# 51PCB_Project.net
KiCad netlist of a schematic drawn in EasyEDA Pro
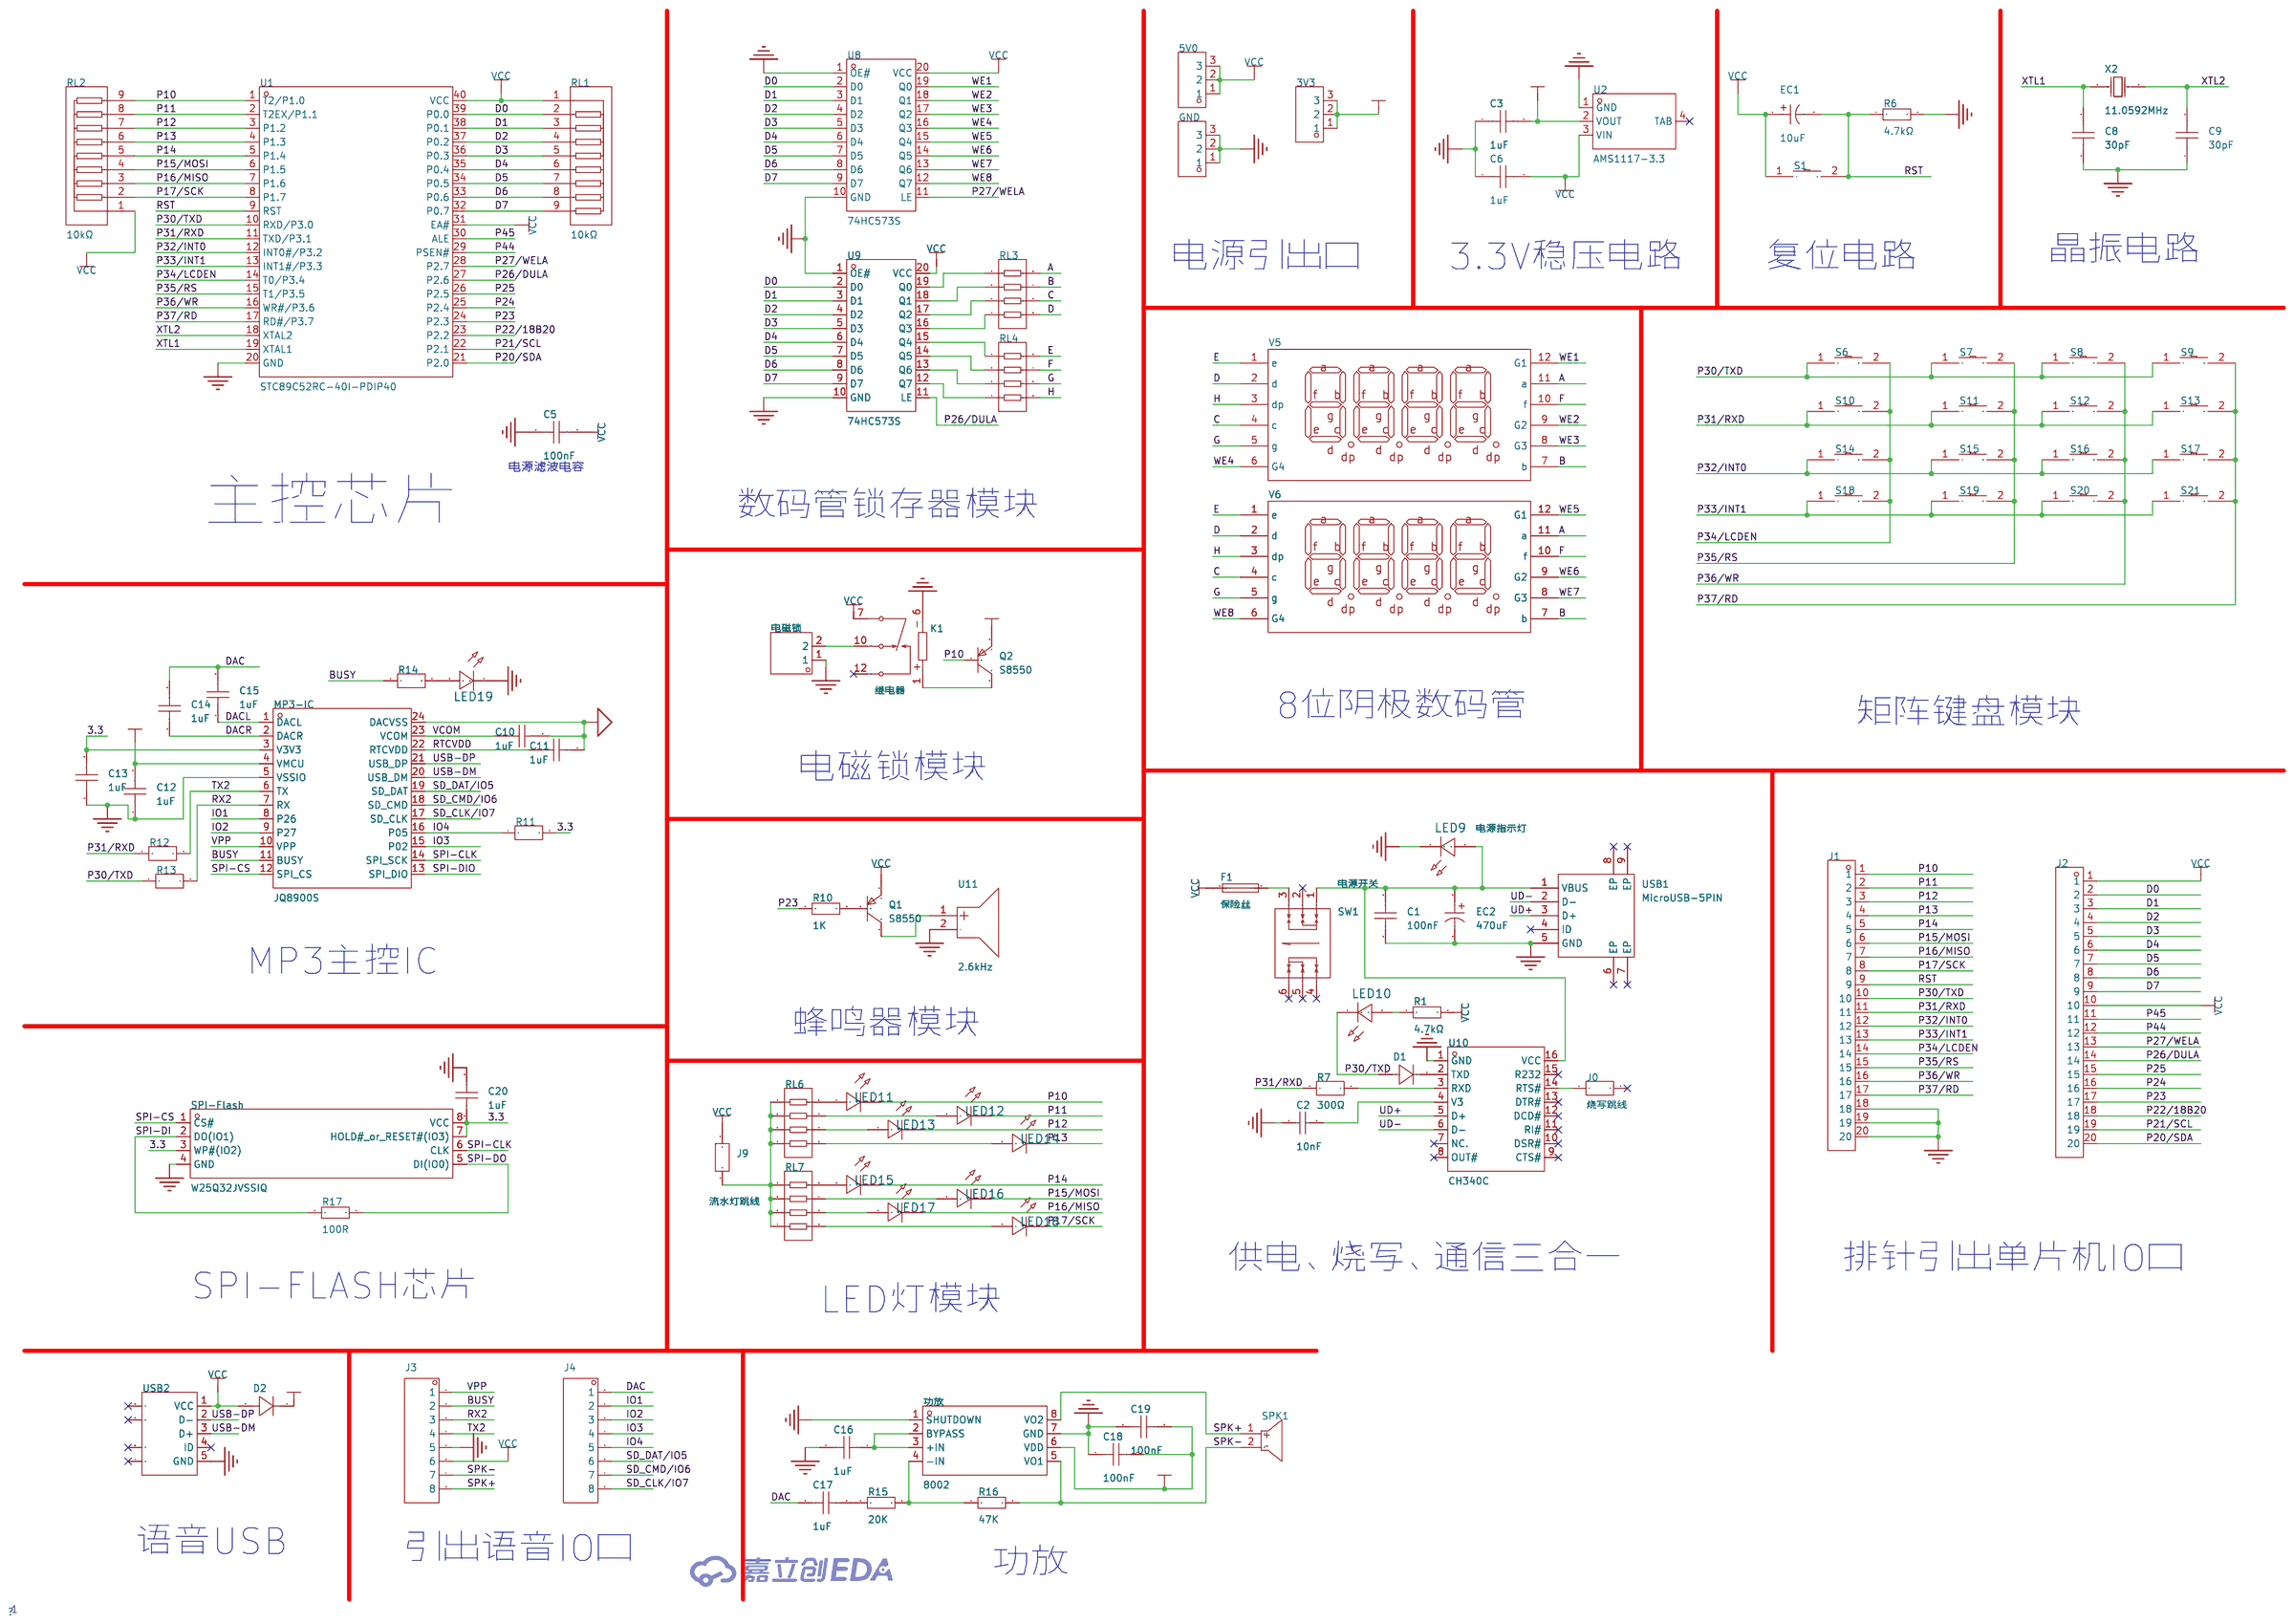
[diagram p0: schematic sheet]

(export (version "E")
  (design (tool "Eeschema 10.0.6"))
  (components
    (comp (ref "3V3")
      (value "~")
      (footprint "easyedapro:HDR-TH_3P-P2.54-V-M")
      (libsource (lib "easyedapro") (part "PZ254V-11-03P_C2937625"))
    )
    (comp (ref "5V0")
      (value "~")
      (footprint "easyedapro:HDR-TH_3P-P2.54-V-M")
      (libsource (lib "easyedapro") (part "PZ254V-11-03P_C2937625"))
    )
    (comp (ref "C1")
      (value "100nF")
      (footprint "easyedapro:CAP-TH_L6.5-W3.5-P2.50-D0.6-S2.90")
      (description "容值:100nF;精度:-20%~+80%;额定电压:50V;温度系数:Y5V;")
      (fields
        (field (name "Manufacturer Part") "CC1H104ZA1FD3F6C1100")
        (field (name "Manufacturer") "Dersonic(德尔创)")
      )
      (libsource (lib "easyedapro") (part "CC1H104ZA1FD3F6C1100"))
    )
    (comp (ref "C2")
      (value "10nF")
      (footprint "easyedapro:C1206")
      (description "容值:10nF;精度:±10%;额定电压:50V;材质(温度系数):X7R;")
      (fields (field (name "Manufacturer Part") "1206B103K500NT") (field (name "Manufacturer") "FH(风华)"))
      (libsource (lib "easyedapro") (part "1206B103K500NT"))
    )
    (comp (ref "C3")
      (value "1uF")
      (footprint "easyedapro:CAP-TH_L5.5-W3.5-P5.00-D1.2")
      (description "容值:1uF;精度:±10%;额定电压:50V;温度系数:X7R;")
      (fields (field (name "Manufacturer Part") "FK26X7R1H105KRE06") (field (name "Manufacturer") "TDK"))
      (libsource (lib "easyedapro") (part "FK26X7R1H105KRE06"))
    )
    (comp (ref "C5")
      (value "100nF")
      (footprint "easyedapro:CAP-TH_L5.0-W2.5-P5.00-D1.0")
      (description "容值:100nF;精度:±20%;额定电压:50V;温度系数:Y5V;")
      (fields
        (field (name "Manufacturer Part") "CC1H104MC1FD3F6C10MF")
        (field (name "Manufacturer") "Dersonic(德尔创)")
      )
      (libsource (lib "easyedapro") (part "CC1H104MC1FD3F6C10MF"))
    )
    (comp (ref "C6")
      (value "1uF")
      (footprint "easyedapro:CAP-TH_L5.5-W3.5-P5.00-D1.2")
      (description "容值:1uF;精度:±10%;额定电压:50V;温度系数:X7R;")
      (fields (field (name "Manufacturer Part") "FK26X7R1H105KRE06") (field (name "Manufacturer") "TDK"))
      (libsource (lib "easyedapro") (part "FK26X7R1H105KRE06"))
    )
    (comp (ref "C8")
      (value "30pF")
      (footprint "easyedapro:CAP-TH_L5.0-W3.0-P5.00-D1.0")
      (description "容值:30pF;精度:±5%;额定电压:50V;温度系数:-;")
      (fields
        (field (name "Manufacturer Part") "DCC300J20COHF6FJ5A0")
        (field (name "Manufacturer") "SHM(南方宏明)")
      )
      (libsource (lib "easyedapro") (part "DCC300J20COHF6FJ5A0"))
    )
    (comp (ref "C9")
      (value "30pF")
      (footprint "easyedapro:CAP-TH_L5.0-W3.0-P5.00-D1.0")
      (description "容值:30pF;精度:±5%;额定电压:50V;温度系数:-;")
      (fields
        (field (name "Manufacturer Part") "DCC300J20COHF6FJ5A0")
        (field (name "Manufacturer") "SHM(南方宏明)")
      )
      (libsource (lib "easyedapro") (part "DCC300J20COHF6FJ5A0"))
    )
    (comp (ref "C10")
      (value "1uF")
      (footprint "easyedapro:CAP-TH_L5.5-W3.5-P5.00-D1.2")
      (description "容值:1uF;精度:±10%;额定电压:50V;温度系数:X7R;")
      (fields (field (name "Manufacturer Part") "FK26X7R1H105KRE06") (field (name "Manufacturer") "TDK"))
      (libsource (lib "easyedapro") (part "FK26X7R1H105KRE06"))
    )
    (comp (ref "C11")
      (value "1uF")
      (footprint "easyedapro:CAP-TH_L5.5-W3.5-P5.00-D1.2")
      (description "容值:1uF;精度:±10%;额定电压:50V;温度系数:X7R;")
      (fields (field (name "Manufacturer Part") "FK26X7R1H105KRE06") (field (name "Manufacturer") "TDK"))
      (libsource (lib "easyedapro") (part "FK26X7R1H105KRE06"))
    )
    (comp (ref "C12")
      (value "1uF")
      (footprint "easyedapro:CAP-TH_L5.5-W3.5-P5.00-D1.2")
      (description "容值:1uF;精度:±10%;额定电压:50V;温度系数:X7R;")
      (fields (field (name "Manufacturer Part") "FK26X7R1H105KRE06") (field (name "Manufacturer") "TDK"))
      (libsource (lib "easyedapro") (part "FK26X7R1H105KRE06"))
    )
    (comp (ref "C13")
      (value "1uF")
      (footprint "easyedapro:CAP-TH_L5.5-W3.5-P5.00-D1.2")
      (description "容值:1uF;精度:±10%;额定电压:50V;温度系数:X7R;")
      (fields (field (name "Manufacturer Part") "FK26X7R1H105KRE06") (field (name "Manufacturer") "TDK"))
      (libsource (lib "easyedapro") (part "FK26X7R1H105KRE06"))
    )
    (comp (ref "C14")
      (value "1uF")
      (footprint "easyedapro:CAP-TH_L5.5-W3.5-P5.00-D1.2")
      (description "容值:1uF;精度:±10%;额定电压:50V;温度系数:X7R;")
      (fields (field (name "Manufacturer Part") "FK26X7R1H105KRE06") (field (name "Manufacturer") "TDK"))
      (libsource (lib "easyedapro") (part "FK26X7R1H105KRE06"))
    )
    (comp (ref "C15")
      (value "1uF")
      (footprint "easyedapro:CAP-TH_L5.5-W3.5-P5.00-D1.2")
      (description "容值:1uF;精度:±10%;额定电压:50V;温度系数:X7R;")
      (fields (field (name "Manufacturer Part") "FK26X7R1H105KRE06") (field (name "Manufacturer") "TDK"))
      (libsource (lib "easyedapro") (part "FK26X7R1H105KRE06"))
    )
    (comp (ref "C16")
      (value "1uF")
      (footprint "easyedapro:CAP-TH_L5.5-W3.5-P5.00-D1.2")
      (description "容值:1uF;精度:±10%;额定电压:50V;温度系数:X7R;")
      (fields (field (name "Manufacturer Part") "FK26X7R1H105KRE06") (field (name "Manufacturer") "TDK"))
      (libsource (lib "easyedapro") (part "FK26X7R1H105KRE06"))
    )
    (comp (ref "C17")
      (value "1uF")
      (footprint "easyedapro:CAP-TH_L5.5-W3.5-P5.00-D1.2")
      (description "容值:1uF;精度:±10%;额定电压:50V;温度系数:X7R;")
      (fields (field (name "Manufacturer Part") "FK26X7R1H105KRE06") (field (name "Manufacturer") "TDK"))
      (libsource (lib "easyedapro") (part "FK26X7R1H105KRE06"))
    )
    (comp (ref "C18")
      (value "100nF")
      (footprint "easyedapro:C0603")
      (libsource (lib "easyedapro") (part "CapAcitance"))
    )
    (comp (ref "C19")
      (value "100nF")
      (footprint "easyedapro:C0603")
      (libsource (lib "easyedapro") (part "CapAcitance"))
    )
    (comp (ref "C20")
      (value "1uF")
      (footprint "easyedapro:CAP-TH_L5.5-W3.5-P5.00-D1.2")
      (description "容值:1uF;精度:±10%;额定电压:50V;温度系数:X7R;")
      (fields (field (name "Manufacturer Part") "FK26X7R1H105KRE06") (field (name "Manufacturer") "TDK"))
      (libsource (lib "easyedapro") (part "FK26X7R1H105KRE06"))
    )
    (comp (ref "D1")
      (value "~")
      (footprint "easyedapro:DO_1N4007")
      (libsource (lib "easyedapro") (part "D_1N4007"))
    )
    (comp (ref "D2")
      (value "~")
      (footprint "easyedapro:DO_1N4007")
      (libsource (lib "easyedapro") (part "D_1N4007"))
    )
    (comp (ref "EC1")
      (value "10uF")
      (footprint "easyedapro:CAP-SMD_BD6.3-L6.6-W6.6-LS7.2-FD")
      (description "容值:10uF;精度:±20%;额定电压:50V;纹波电流:29mA@120Hz;")
      (fields
        (field (name "Manufacturer Part") "MVK50V10M6.3*5")
        (field (name "Manufacturer") "SAMYOUNG(韩国三莹)")
      )
      (libsource (lib "easyedapro") (part "MVK50V10UF06*05"))
    )
    (comp (ref "EC2")
      (value "470uF")
      (footprint "easyedapro:CAP-TH_BD16.0-P7.50-D1.2-FD")
      (description "容值:470uF;精度:±20%;额定电压:100V;纹波电流:2.4A@100kHz;等效串联电阻:33mΩ@100kHz;")
      (fields
        (field (name "Manufacturer Part") "NXH100VB470M16*31.5 LO")
        (field (name "Manufacturer") "SAMYOUNG(韩国三莹)")
      )
      (libsource (lib "easyedapro") (part "NXH100VB470M16*31.5 LO"))
    )
    (comp (ref "F1")
      (value "保险丝")
      (footprint "easyedapro:F1812")
      (description "最大电压:33V;最大电流:40A;保持电流:500mA;跳闸电流:1A;")
      (fields (field (name "Manufacturer") "BHFUSE(佰宏)"))
      (libsource (lib "easyedapro") (part "BSMD1812-050-33V"))
    )
    (comp (ref "GND")
      (value "~")
      (footprint "easyedapro:HDR-TH_3P-P2.54-V-M")
      (libsource (lib "easyedapro") (part "PZ254V-11-03P_C2937625"))
    )
    (comp (ref "J0")
      (value "烧写跳线")
      (footprint "easyedapro:CONN-TH_D3086XX")
      (fields (field (name "Manufacturer Part") "D3086-97") (field (name "Manufacturer") "Harwin"))
      (libsource (lib "easyedapro") (part "D3086-97"))
    )
    (comp (ref "J1")
      (value "~")
      (footprint "easyedapro:HDR-TH_20P-P2.54-V-M-1")
      (libsource (lib "easyedapro") (part "HDR_2.54-1x20P"))
    )
    (comp (ref "J2")
      (value "~")
      (footprint "easyedapro:HDR-TH_20P-P2.54-V-M-1")
      (libsource (lib "easyedapro") (part "HDR_2.54-1x20P"))
    )
    (comp (ref "J3")
      (value "~")
      (footprint "easyedapro:HDR-TH_8P-P2.54-V-M")
      (libsource (lib "easyedapro") (part "Header-Male-2.54_1x8"))
    )
    (comp (ref "J4")
      (value "~")
      (footprint "easyedapro:HDR-TH_8P-P2.54-V-M")
      (libsource (lib "easyedapro") (part "Header-Male-2.54_1x8"))
    )
    (comp (ref "J9")
      (value "流水灯跳线")
      (footprint "easyedapro:CONN-TH_D3086XX")
      (fields (field (name "Manufacturer") "Harwin"))
      (libsource (lib "easyedapro") (part "D3086-97"))
    )
    (comp (ref "K1")
      (value "继电器")
      (footprint "easyedapro:RELAY-TH_DS1E-S-DC24V")
      (description "线圈电压:12V;触点形式:一组转换:1C(单刀双掷-转换);触点容量(电阻负载):-;最大切换电压:250V@AC；220V@DC;最大切换电流:2A;")
      (fields (field (name "Manufacturer") "PANASONIC(松下)"))
      (libsource (lib "easyedapro") (part "DS1E-M-DC12V"))
    )
    (comp (ref "LED9")
      (value "电源指示灯")
      (footprint "easyedapro:LED_0805")
      (libsource (lib "easyedapro") (part "LED_R"))
    )
    (comp (ref "LED10")
      (value "~")
      (footprint "easyedapro:LED_0805")
      (libsource (lib "easyedapro") (part "LED_R"))
    )
    (comp (ref "LED11")
      (value "~")
      (footprint "easyedapro:LED_0805")
      (libsource (lib "easyedapro") (part "LED_R"))
    )
    (comp (ref "LED12")
      (value "~")
      (footprint "easyedapro:LED_0805")
      (libsource (lib "easyedapro") (part "LED_R"))
    )
    (comp (ref "LED13")
      (value "~")
      (footprint "easyedapro:LED_0805")
      (libsource (lib "easyedapro") (part "LED_R"))
    )
    (comp (ref "LED14")
      (value "~")
      (footprint "easyedapro:LED_0805")
      (libsource (lib "easyedapro") (part "LED_R"))
    )
    (comp (ref "LED15")
      (value "~")
      (footprint "easyedapro:LED_0805")
      (libsource (lib "easyedapro") (part "LED_R"))
    )
    (comp (ref "LED16")
      (value "~")
      (footprint "easyedapro:LED_0805")
      (libsource (lib "easyedapro") (part "LED_R"))
    )
    (comp (ref "LED17")
      (value "~")
      (footprint "easyedapro:LED_0805")
      (libsource (lib "easyedapro") (part "LED_R"))
    )
    (comp (ref "LED18")
      (value "~")
      (footprint "easyedapro:LED_0805")
      (libsource (lib "easyedapro") (part "LED_R"))
    )
    (comp (ref "LED19")
      (value "~")
      (footprint "easyedapro:LED_0805")
      (libsource (lib "easyedapro") (part "LED_R"))
    )
    (comp (ref "MP3-IC")
      (value "JQ8900S")
      (footprint "easyedapro:TSSOP-24_L7.8-W4.4-P0.65-LS6.4-BL_1")
      (libsource (lib "easyedapro") (part "JQ8900S"))
    )
    (comp (ref "Q1")
      (value "S8550")
      (footprint "easyedapro:SOT-23-3_L2.9-W1.3-P1.90-LS2.4-BR")
      (fields (field (name "Manufacturer") "Doeshare(德芯)"))
      (libsource (lib "easyedapro") (part "S8550_C2931720"))
    )
    (comp (ref "Q2")
      (value "S8550")
      (footprint "easyedapro:SOT-23-3_L2.9-W1.3-P1.90-LS2.4-BR")
      (fields (field (name "Manufacturer") "Doeshare(德芯)"))
      (libsource (lib "easyedapro") (part "S8550_C2931720"))
    )
    (comp (ref "R1")
      (value "4.7kΩ")
      (footprint "easyedapro:R1206")
      (description "电阻类型:厚膜电阻;阻值:4.7kΩ;精度:±1%;功率:250mW;最大工作电压:200V;温度系数:±100ppm/°C;")
      (fields
        (field (name "Manufacturer Part") "1206W4F4701T5E")
        (field (name "Manufacturer") "UNI-ROYAL(厚声)")
      )
      (libsource (lib "easyedapro") (part "1206W4F4701T5E"))
    )
    (comp (ref "R6")
      (value "4.7kΩ")
      (footprint "easyedapro:RES-TH_BD1.9-L3.3-P7.30-D0.5")
      (description "电阻类型:金属膜电阻;阻值:4.7kΩ;精度:±1%;功率:125mW;温度系数:±50ppm/°C;")
      (fields
        (field (name "Manufacturer Part") "MFR0W8F4701A50")
        (field (name "Manufacturer") "UNI-ROYAL(厚声)")
      )
      (libsource (lib "easyedapro") (part "MFR0W8F4701A50"))
    )
    (comp (ref "R7")
      (value "300Ω")
      (footprint "easyedapro:R1206")
      (description "电阻类型:厚膜电阻;阻值:300Ω;精度:±5%;功率:250mW;最大工作电压:200V;温度系数:±100ppm/°C;")
      (fields (field (name "Manufacturer Part") "FRC1206J301 TS") (field (name "Manufacturer") "FOJAN(富捷)"))
      (libsource (lib "easyedapro") (part "FRC1206J301 TS"))
    )
    (comp (ref "R10") (value "1K") (footprint "easyedapro:R1206") (libsource (lib "easyedapro") (part "电阻")))
    (comp (ref "R11")
      (value "300Ω")
      (footprint "easyedapro:R1206")
      (description "电阻类型:厚膜电阻;阻值:300Ω;精度:±5%;功率:250mW;最大工作电压:200V;温度系数:±100ppm/°C;")
      (fields (field (name "Manufacturer Part") "FRC1206J301 TS") (field (name "Manufacturer") "FOJAN(富捷)"))
      (libsource (lib "easyedapro") (part "FRC1206J301 TS"))
    )
    (comp (ref "R12")
      (value "300Ω")
      (footprint "easyedapro:R1206")
      (description "电阻类型:厚膜电阻;阻值:300Ω;精度:±5%;功率:250mW;最大工作电压:200V;温度系数:±100ppm/°C;")
      (fields (field (name "Manufacturer Part") "FRC1206J301 TS") (field (name "Manufacturer") "FOJAN(富捷)"))
      (libsource (lib "easyedapro") (part "FRC1206J301 TS"))
    )
    (comp (ref "R13")
      (value "300Ω")
      (footprint "easyedapro:R1206")
      (description "电阻类型:厚膜电阻;阻值:300Ω;精度:±5%;功率:250mW;最大工作电压:200V;温度系数:±100ppm/°C;")
      (fields (field (name "Manufacturer Part") "FRC1206J301 TS") (field (name "Manufacturer") "FOJAN(富捷)"))
      (libsource (lib "easyedapro") (part "FRC1206J301 TS"))
    )
    (comp (ref "R14")
      (value "300Ω")
      (footprint "easyedapro:R1206")
      (description "电阻类型:厚膜电阻;阻值:300Ω;精度:±5%;功率:250mW;最大工作电压:200V;温度系数:±100ppm/°C;")
      (fields (field (name "Manufacturer Part") "FRC1206J301 TS") (field (name "Manufacturer") "FOJAN(富捷)"))
      (libsource (lib "easyedapro") (part "FRC1206J301 TS"))
    )
    (comp (ref "R15") (value "20K") (footprint "easyedapro:R1206") (libsource (lib "easyedapro") (part "电阻")))
    (comp (ref "R16") (value "47K") (footprint "easyedapro:R1206") (libsource (lib "easyedapro") (part "电阻")))
    (comp (ref "R17")
      (value "100R")
      (footprint "easyedapro:R1206")
      (libsource (lib "easyedapro") (part "电阻"))
    )
    (comp (ref "RL1")
      (value "10kΩ")
      (footprint "easyedapro:RES-ARRAY-TH_9P-P2.54-D1.0")
      (description "电阻器数:8;阻值:10kΩ;精度:±2%;单个元件功率:125mW;温度系数:±100ppm/°C;")
      (fields (field (name "Manufacturer Part") "A09-103GP") (field (name "Manufacturer") "FH(风华)"))
      (libsource (lib "easyedapro") (part "A09-103GP"))
    )
    (comp (ref "RL2")
      (value "10kΩ")
      (footprint "easyedapro:RES-ARRAY-TH_9P-P2.54-D1.0")
      (description "电阻器数:8;阻值:10kΩ;精度:±2%;单个元件功率:125mW;温度系数:±100ppm/°C;")
      (fields (field (name "Manufacturer Part") "A09-103GP") (field (name "Manufacturer") "FH(风华)"))
      (libsource (lib "easyedapro") (part "A09-103GP"))
    )
    (comp (ref "RL3")
      (value "470Ω")
      (footprint "easyedapro:RES-ARRAY-TH_8P-P2.54-D1.0")
      (description "电阻器数:4;阻值:470Ω;精度:±2%;单个元件功率:300mW;温度系数:±100ppm/°C;")
      (fields (field (name "Manufacturer Part") "4608X-102-471LF") (field (name "Manufacturer") "BOURNS"))
      (libsource (lib "easyedapro") (part "4608X-102-471LF"))
    )
    (comp (ref "RL4")
      (value "470Ω")
      (footprint "easyedapro:RES-ARRAY-TH_8P-P2.54-D1.0")
      (description "电阻器数:4;阻值:470Ω;精度:±2%;单个元件功率:300mW;温度系数:±100ppm/°C;")
      (fields (field (name "Manufacturer Part") "4608X-102-471LF") (field (name "Manufacturer") "BOURNS"))
      (libsource (lib "easyedapro") (part "4608X-102-471LF"))
    )
    (comp (ref "RL6")
      (value "470Ω")
      (footprint "easyedapro:RES-ARRAY-TH_8P-P2.54-D1.0")
      (description "电阻器数:4;阻值:470Ω;精度:±2%;单个元件功率:300mW;温度系数:±100ppm/°C;")
      (fields (field (name "Manufacturer Part") "4608X-102-471LF") (field (name "Manufacturer") "BOURNS"))
      (libsource (lib "easyedapro") (part "4608X-102-471LF"))
    )
    (comp (ref "RL7")
      (value "470Ω")
      (footprint "easyedapro:RES-ARRAY-TH_8P-P2.54-D1.0")
      (description "电阻器数:4;阻值:470Ω;精度:±2%;单个元件功率:300mW;温度系数:±100ppm/°C;")
      (fields (field (name "Manufacturer Part") "4608X-102-471LF") (field (name "Manufacturer") "BOURNS"))
      (libsource (lib "easyedapro") (part "4608X-102-471LF"))
    )
    (comp (ref "S1")
      (value "TS-1101-C-W")
      (footprint "easyedapro:SW-SMD_L6.0-W3.3-LS8.0")
      (fields (field (name "Manufacturer") "XKB Connectivity(中国星坤)"))
      (libsource (lib "easyedapro") (part "TS-1101-C-W"))
    )
    (comp (ref "S6")
      (value "TS-1101-C-W")
      (footprint "easyedapro:SW-SMD_L6.0-W3.3-LS8.0")
      (fields (field (name "Manufacturer") "XKB Connectivity(中国星坤)"))
      (libsource (lib "easyedapro") (part "TS-1101-C-W"))
    )
    (comp (ref "S7")
      (value "TS-1101-C-W")
      (footprint "easyedapro:SW-SMD_L6.0-W3.3-LS8.0")
      (fields (field (name "Manufacturer") "XKB Connectivity(中国星坤)"))
      (libsource (lib "easyedapro") (part "TS-1101-C-W"))
    )
    (comp (ref "S8")
      (value "TS-1101-C-W")
      (footprint "easyedapro:SW-SMD_L6.0-W3.3-LS8.0")
      (fields (field (name "Manufacturer") "XKB Connectivity(中国星坤)"))
      (libsource (lib "easyedapro") (part "TS-1101-C-W"))
    )
    (comp (ref "S9")
      (value "TS-1101-C-W")
      (footprint "easyedapro:SW-SMD_L6.0-W3.3-LS8.0")
      (fields (field (name "Manufacturer") "XKB Connectivity(中国星坤)"))
      (libsource (lib "easyedapro") (part "TS-1101-C-W"))
    )
    (comp (ref "S10")
      (value "TS-1101-C-W")
      (footprint "easyedapro:SW-SMD_L6.0-W3.3-LS8.0")
      (fields (field (name "Manufacturer") "XKB Connectivity(中国星坤)"))
      (libsource (lib "easyedapro") (part "TS-1101-C-W"))
    )
    (comp (ref "S11")
      (value "TS-1101-C-W")
      (footprint "easyedapro:SW-SMD_L6.0-W3.3-LS8.0")
      (fields (field (name "Manufacturer") "XKB Connectivity(中国星坤)"))
      (libsource (lib "easyedapro") (part "TS-1101-C-W"))
    )
    (comp (ref "S12")
      (value "TS-1101-C-W")
      (footprint "easyedapro:SW-SMD_L6.0-W3.3-LS8.0")
      (fields (field (name "Manufacturer") "XKB Connectivity(中国星坤)"))
      (libsource (lib "easyedapro") (part "TS-1101-C-W"))
    )
    (comp (ref "S13")
      (value "TS-1101-C-W")
      (footprint "easyedapro:SW-SMD_L6.0-W3.3-LS8.0")
      (fields (field (name "Manufacturer") "XKB Connectivity(中国星坤)"))
      (libsource (lib "easyedapro") (part "TS-1101-C-W"))
    )
    (comp (ref "S14")
      (value "TS-1101-C-W")
      (footprint "easyedapro:SW-SMD_L6.0-W3.3-LS8.0")
      (fields (field (name "Manufacturer") "XKB Connectivity(中国星坤)"))
      (libsource (lib "easyedapro") (part "TS-1101-C-W"))
    )
    (comp (ref "S15")
      (value "TS-1101-C-W")
      (footprint "easyedapro:SW-SMD_L6.0-W3.3-LS8.0")
      (fields (field (name "Manufacturer") "XKB Connectivity(中国星坤)"))
      (libsource (lib "easyedapro") (part "TS-1101-C-W"))
    )
    (comp (ref "S16")
      (value "TS-1101-C-W")
      (footprint "easyedapro:SW-SMD_L6.0-W3.3-LS8.0")
      (fields (field (name "Manufacturer") "XKB Connectivity(中国星坤)"))
      (libsource (lib "easyedapro") (part "TS-1101-C-W"))
    )
    (comp (ref "S17")
      (value "TS-1101-C-W")
      (footprint "easyedapro:SW-SMD_L6.0-W3.3-LS8.0")
      (fields (field (name "Manufacturer") "XKB Connectivity(中国星坤)"))
      (libsource (lib "easyedapro") (part "TS-1101-C-W"))
    )
    (comp (ref "S18")
      (value "TS-1101-C-W")
      (footprint "easyedapro:SW-SMD_L6.0-W3.3-LS8.0")
      (fields (field (name "Manufacturer") "XKB Connectivity(中国星坤)"))
      (libsource (lib "easyedapro") (part "TS-1101-C-W"))
    )
    (comp (ref "S19")
      (value "TS-1101-C-W")
      (footprint "easyedapro:SW-SMD_L6.0-W3.3-LS8.0")
      (fields (field (name "Manufacturer") "XKB Connectivity(中国星坤)"))
      (libsource (lib "easyedapro") (part "TS-1101-C-W"))
    )
    (comp (ref "S20")
      (value "TS-1101-C-W")
      (footprint "easyedapro:SW-SMD_L6.0-W3.3-LS8.0")
      (fields (field (name "Manufacturer") "XKB Connectivity(中国星坤)"))
      (libsource (lib "easyedapro") (part "TS-1101-C-W"))
    )
    (comp (ref "S21")
      (value "TS-1101-C-W")
      (footprint "easyedapro:SW-SMD_L6.0-W3.3-LS8.0")
      (fields (field (name "Manufacturer") "XKB Connectivity(中国星坤)"))
      (libsource (lib "easyedapro") (part "TS-1101-C-W"))
    )
    (comp (ref "SPI-Flash")
      (value "W25Q32JVSSIQ")
      (footprint "easyedapro:SOIC-8_L5.3-W5.3-P1.27-LS8.0-BL")
      (fields (field (name "Manufacturer") "WINBOND(华邦)"))
      (libsource (lib "easyedapro") (part "W25Q32JVSSIQ_C179173"))
    )
    (comp (ref "SPK1")
      (value "FS-2308")
      (footprint "easyedapro:BEEP-TH_BD23.2-P9.20-D1.0")
      (fields (field (name "Manufacturer") "FUET(福声科技)"))
      (libsource (lib "easyedapro") (part "FS-2308"))
    )
    (comp (ref "SW1")
      (value "电源开关")
      (footprint "easyedapro:SW-TH_6P-L8.0-W8.0-P2.50")
      (description "电路结构:双刀双掷;自锁/无锁:自锁;安装方式:直插;触点电流:100mA;额定电压 (AC):-;额定电压 (DC):30V;带灯:不带;作用力:180gf;机械寿命:5千次;")
      (fields (field (name "Manufacturer") "SHOU HAN(首韩)"))
      (libsource (lib "easyedapro") (part "8-8 ZS"))
    )
    (comp (ref "U1")
      (value "STC89C52RC-40I-PDIP40")
      (footprint "easyedapro:DIP-40_L52.0-W13.7-P2.54-LS15.2-BL")
      (description "CPU内核:51系列;程序存储容量:8KB;RAM总容量:512Byte;GPIO端口数量:35;工作电压范围:3.3V~5.5V;CPU最大主频:-;程序存储器类型:FLASH;")
      (fields (field (name "Manufacturer") "STC(宏晶)"))
      (libsource (lib "easyedapro") (part "STC89C52RC-40I"))
    )
    (comp (ref "U2")
      (value "AMS1117-3.3")
      (footprint "easyedapro:SOT-223-3_L6.5-W3.5-P3.05-LS7.0")
      (description "输出类型:固定;工作电压:12V;输出电压:3.3V;输出电流:1A;电源纹波抑制比(PSRR):70dB@(120Hz);输出极性:正极;")
      (fields (field (name "Manufacturer") "TWGMC(台湾迪嘉)"))
      (libsource (lib "easyedapro") (part "AMS1117-3.3_C5250992"))
    )
    (comp (ref "U8")
      (value "74HC573S")
      (footprint "easyedapro:SOIC-20_L13.0-W7.6-P1.27-LS10.3-BL")
      (fields (field (name "Manufacturer") "GR(国睿)"))
      (libsource (lib "easyedapro") (part "74HC573S"))
    )
    (comp (ref "U9")
      (value "74HC573S")
      (footprint "easyedapro:SOIC-20_L13.0-W7.6-P1.27-LS10.3-BL")
      (fields (field (name "Manufacturer") "GR(国睿)"))
      (libsource (lib "easyedapro") (part "74HC573S"))
    )
    (comp (ref "U10")
      (value "CH340C")
      (footprint "easyedapro:SOP-16_L10.0-W3.9-P1.27-LS6.0-BL")
      (description "应用功能:收发器;接口协议:USB 2.0;数据速率:2Mbps;")
      (fields (field (name "Manufacturer") "WCH(南京沁恒)"))
      (libsource (lib "easyedapro") (part "CH340C"))
    )
    (comp (ref "U11")
      (value "2.6kHz")
      (footprint "easyedapro:BUZ-TH_BD12.0-P7.60-D0.6-FD")
      (description "频率:2.6kHz;声压(SPL):85dB@12V,10cm;")
      (fields (field (name "Manufacturer Part") "HYE1206-12ST") (field (name "Manufacturer") "HYDZ(华宇)"))
      (libsource (lib "easyedapro") (part "HYE1206-12ST"))
    )
    (comp (ref "USB1")
      (value "MicroUSB-5PIN")
      (footprint "easyedapro:USB-SMD_5P_MICROUSB-5PIN")
      (libsource (lib "easyedapro") (part "MICROUSB-5PIN"))
    )
    (comp (ref "USB2")
      (value "~")
      (footprint "easyedapro:USB_MINI-5P")
      (libsource (lib "easyedapro") (part "MINI 5PTP"))
    )
    (comp (ref "V5")
      (value "FJ3461AH")
      (footprint "easyedapro:LED-SEG-TH_12P-L30.0-W14.0-P2.54-S10.16-BL")
      (description "数码管位数:4位;功耗:-;发光颜色:红色;LED极性:共阴极;数字/字母大小(英寸):0.36;")
      (fields (field (name "Manufacturer") "志浩"))
      (libsource (lib "easyedapro") (part "FJ3461AH"))
    )
    (comp (ref "V6")
      (value "FJ3461AH")
      (footprint "easyedapro:LED-SEG-TH_12P-L30.0-W14.0-P2.54-S10.16-BL")
      (description "数码管位数:4位;功耗:-;发光颜色:红色;LED极性:共阴极;数字/字母大小(英寸):0.36;")
      (fields (field (name "Manufacturer") "志浩"))
      (libsource (lib "easyedapro") (part "FJ3461AH"))
    )
    (comp (ref "X2")
      (value "11.0592MHz")
      (footprint "easyedapro:HC-49US_L11.5-W4.5-P4.88")
      (description "晶振类型:直插晶振;频率:11.0592MHz;常温频差:±20ppm;外接负载电容:20pF;频率稳定度(全温):±30ppm;")
      (fields
        (field (name "Manufacturer Part") "X49SD110592MSD2SC")
        (field (name "Manufacturer") "YXC(扬兴晶振)")
      )
      (libsource (lib "easyedapro") (part "X49SD110592MSD2SC"))
    )
    (comp (ref "功放")
      (value "8002")
      (footprint "easyedapro:SOP-8_L4.9-W3.9-P1.27-LS6.0-BL")
      (description "功率放大器")
      (fields (field (name "Manufacturer") "I-CORE(中微爱芯)"))
      (libsource (lib "easyedapro") (part "8002"))
    )
    (comp (ref "电磁锁")
      (value "~")
      (footprint "easyedapro:HDR-TH_2P-P2.54-V-M-1")
      (libsource (lib "easyedapro") (part "210S-1*2P L=11.6MMGold-plated black"))
    )
  )
  (nets
    (net (code "1") (name "+3.3") (class "Default")
      (node (ref "3V3") (pin "1") (pinfunction "1_1") (pintype "input"))
      (node (ref "3V3") (pin "2") (pinfunction "2_2") (pintype "input"))
      (node (ref "3V3") (pin "3") (pinfunction "3_3") (pintype "input"))
      (node (ref "C3") (pin "2") (pinfunction "2_2") (pintype "unspecified"))
      (node (ref "Q2") (pin "2") (pinfunction "E_2") (pintype "unspecified"))
      (node (ref "U2") (pin "2") (pinfunction "VOUT_2") (pintype "unspecified"))
    )
    (net (code "2") (name "/3.3") (class "Default")
      (node (ref "C13") (pin "2") (pinfunction "2_2") (pintype "unspecified"))
      (node (ref "C20") (pin "2") (pinfunction "2_2") (pintype "unspecified"))
      (node (ref "MP3-IC") (pin "3") (pinfunction "V3V3_3") (pintype "unspecified"))
      (node (ref "R11") (pin "2") (pinfunction "2_2") (pintype "unspecified"))
      (node (ref "SPI-Flash") (pin "3") (pinfunction "WP#(IO2)_3") (pintype "unspecified"))
      (node (ref "SPI-Flash") (pin "7") (pinfunction "HOLD#_or_RESET#(IO3)_7") (pintype "unspecified"))
      (node (ref "SPI-Flash") (pin "8") (pinfunction "VCC_8") (pintype "unspecified"))
    )
    (net (code "3") (name "/A") (class "Default")
      (node (ref "RL3") (pin "8") (pinfunction "8_8") (pintype "unspecified"))
      (node (ref "V5") (pin "11") (pinfunction "a_11") (pintype "input"))
      (node (ref "V6") (pin "11") (pinfunction "a_11") (pintype "input"))
    )
    (net (code "4") (name "/B") (class "Default")
      (node (ref "RL3") (pin "7") (pinfunction "7_7") (pintype "unspecified"))
      (node (ref "V5") (pin "7") (pinfunction "b_7") (pintype "input"))
      (node (ref "V6") (pin "7") (pinfunction "b_7") (pintype "input"))
    )
    (net (code "5") (name "/BUSY") (class "Default")
      (node (ref "J3") (pin "2") (pinfunction "2_2") (pintype "unspecified"))
      (node (ref "MP3-IC") (pin "11") (pinfunction "BUSY_11") (pintype "unspecified"))
      (node (ref "R14") (pin "1") (pinfunction "1_1") (pintype "unspecified"))
    )
    (net (code "6") (name "/C") (class "Default")
      (node (ref "RL3") (pin "6") (pinfunction "6_6") (pintype "unspecified"))
      (node (ref "V5") (pin "4") (pinfunction "c_4") (pintype "input"))
      (node (ref "V6") (pin "4") (pinfunction "c_4") (pintype "input"))
    )
    (net (code "7") (name "/D") (class "Default")
      (node (ref "RL3") (pin "5") (pinfunction "5_5") (pintype "unspecified"))
      (node (ref "V5") (pin "2") (pinfunction "d_2") (pintype "input"))
      (node (ref "V6") (pin "2") (pinfunction "d_2") (pintype "input"))
    )
    (net (code "8") (name "/D0") (class "Default")
      (node (ref "J2") (pin "2") (pinfunction "2_2") (pintype "input"))
      (node (ref "RL1") (pin "2") (pinfunction "2_2") (pintype "unspecified"))
      (node (ref "U1") (pin "39") (pinfunction "P0.0_39") (pintype "unspecified"))
      (node (ref "U8") (pin "2") (pinfunction "D0_2") (pintype "unspecified"))
      (node (ref "U9") (pin "2") (pinfunction "D0_2") (pintype "unspecified"))
    )
    (net (code "9") (name "/D1") (class "Default")
      (node (ref "J2") (pin "3") (pinfunction "3_3") (pintype "input"))
      (node (ref "RL1") (pin "3") (pinfunction "3_3") (pintype "unspecified"))
      (node (ref "U1") (pin "38") (pinfunction "P0.1_38") (pintype "unspecified"))
      (node (ref "U8") (pin "3") (pinfunction "D1_3") (pintype "unspecified"))
      (node (ref "U9") (pin "3") (pinfunction "D1_3") (pintype "unspecified"))
    )
    (net (code "10") (name "/D2") (class "Default")
      (node (ref "J2") (pin "4") (pinfunction "4_4") (pintype "input"))
      (node (ref "RL1") (pin "4") (pinfunction "4_4") (pintype "unspecified"))
      (node (ref "U1") (pin "37") (pinfunction "P0.2_37") (pintype "unspecified"))
      (node (ref "U8") (pin "4") (pinfunction "D2_4") (pintype "unspecified"))
      (node (ref "U9") (pin "4") (pinfunction "D2_4") (pintype "unspecified"))
    )
    (net (code "11") (name "/D3") (class "Default")
      (node (ref "J2") (pin "5") (pinfunction "5_5") (pintype "input"))
      (node (ref "RL1") (pin "5") (pinfunction "5_5") (pintype "unspecified"))
      (node (ref "U1") (pin "36") (pinfunction "P0.3_36") (pintype "unspecified"))
      (node (ref "U8") (pin "5") (pinfunction "D3_5") (pintype "unspecified"))
      (node (ref "U9") (pin "5") (pinfunction "D3_5") (pintype "unspecified"))
    )
    (net (code "12") (name "/D4") (class "Default")
      (node (ref "J2") (pin "6") (pinfunction "6_6") (pintype "input"))
      (node (ref "RL1") (pin "6") (pinfunction "6_6") (pintype "unspecified"))
      (node (ref "U1") (pin "35") (pinfunction "P0.4_35") (pintype "unspecified"))
      (node (ref "U8") (pin "6") (pinfunction "D4_6") (pintype "unspecified"))
      (node (ref "U9") (pin "6") (pinfunction "D4_6") (pintype "unspecified"))
    )
    (net (code "13") (name "/D5") (class "Default")
      (node (ref "J2") (pin "7") (pinfunction "7_7") (pintype "input"))
      (node (ref "RL1") (pin "7") (pinfunction "7_7") (pintype "unspecified"))
      (node (ref "U1") (pin "34") (pinfunction "P0.5_34") (pintype "unspecified"))
      (node (ref "U8") (pin "7") (pinfunction "D5_7") (pintype "unspecified"))
      (node (ref "U9") (pin "7") (pinfunction "D5_7") (pintype "unspecified"))
    )
    (net (code "14") (name "/D6") (class "Default")
      (node (ref "J2") (pin "8") (pinfunction "8_8") (pintype "input"))
      (node (ref "RL1") (pin "8") (pinfunction "8_8") (pintype "unspecified"))
      (node (ref "U1") (pin "33") (pinfunction "P0.6_33") (pintype "unspecified"))
      (node (ref "U8") (pin "8") (pinfunction "D6_8") (pintype "unspecified"))
      (node (ref "U9") (pin "8") (pinfunction "D6_8") (pintype "unspecified"))
    )
    (net (code "15") (name "/D7") (class "Default")
      (node (ref "J2") (pin "9") (pinfunction "9_9") (pintype "input"))
      (node (ref "RL1") (pin "9") (pinfunction "9_9") (pintype "unspecified"))
      (node (ref "U1") (pin "32") (pinfunction "P0.7_32") (pintype "unspecified"))
      (node (ref "U8") (pin "9") (pinfunction "D7_9") (pintype "unspecified"))
      (node (ref "U9") (pin "9") (pinfunction "D7_9") (pintype "unspecified"))
    )
    (net (code "16") (name "/DAC") (class "Default")
      (node (ref "C14") (pin "2") (pinfunction "2_2") (pintype "unspecified"))
      (node (ref "C15") (pin "2") (pinfunction "2_2") (pintype "unspecified"))
      (node (ref "C17") (pin "2") (pinfunction "2_2") (pintype "unspecified"))
      (node (ref "J4") (pin "1") (pinfunction "1_1") (pintype "unspecified"))
    )
    (net (code "17") (name "/DACL") (class "Default")
      (node (ref "C15") (pin "1") (pinfunction "1_1") (pintype "unspecified"))
      (node (ref "MP3-IC") (pin "1") (pinfunction "DACL_1") (pintype "unspecified"))
    )
    (net (code "18") (name "/DACR") (class "Default")
      (node (ref "C14") (pin "1") (pinfunction "1_1") (pintype "unspecified"))
      (node (ref "MP3-IC") (pin "2") (pinfunction "DACR_2") (pintype "unspecified"))
    )
    (net (code "19") (name "/E") (class "Default")
      (node (ref "RL4") (pin "8") (pinfunction "8_8") (pintype "unspecified"))
      (node (ref "V5") (pin "1") (pinfunction "e_1") (pintype "input"))
      (node (ref "V6") (pin "1") (pinfunction "e_1") (pintype "input"))
    )
    (net (code "20") (name "/F") (class "Default")
      (node (ref "RL4") (pin "7") (pinfunction "7_7") (pintype "unspecified"))
      (node (ref "V5") (pin "10") (pinfunction "f_10") (pintype "input"))
      (node (ref "V6") (pin "10") (pinfunction "f_10") (pintype "input"))
    )
    (net (code "21") (name "/G") (class "Default")
      (node (ref "RL4") (pin "6") (pinfunction "6_6") (pintype "unspecified"))
      (node (ref "V5") (pin "5") (pinfunction "g_5") (pintype "input"))
      (node (ref "V6") (pin "5") (pinfunction "g_5") (pintype "input"))
    )
    (net (code "22") (name "/H") (class "Default")
      (node (ref "RL4") (pin "5") (pinfunction "5_5") (pintype "unspecified"))
      (node (ref "V5") (pin "3") (pinfunction "dp_3") (pintype "input"))
      (node (ref "V6") (pin "3") (pinfunction "dp_3") (pintype "input"))
    )
    (net (code "23") (name "/IO1") (class "Default")
      (node (ref "J4") (pin "2") (pinfunction "2_2") (pintype "unspecified"))
      (node (ref "MP3-IC") (pin "8") (pinfunction "P26_8") (pintype "unspecified"))
    )
    (net (code "24") (name "/IO2") (class "Default")
      (node (ref "J4") (pin "3") (pinfunction "3_3") (pintype "unspecified"))
      (node (ref "MP3-IC") (pin "9") (pinfunction "P27_9") (pintype "unspecified"))
    )
    (net (code "25") (name "/IO3") (class "Default")
      (node (ref "J4") (pin "4") (pinfunction "4_4") (pintype "unspecified"))
      (node (ref "MP3-IC") (pin "15") (pinfunction "P02_15") (pintype "unspecified"))
    )
    (net (code "26") (name "/IO4") (class "Default")
      (node (ref "J4") (pin "5") (pinfunction "5_5") (pintype "unspecified"))
      (node (ref "MP3-IC") (pin "16") (pinfunction "P05_16") (pintype "unspecified"))
      (node (ref "R11") (pin "1") (pinfunction "1_1") (pintype "unspecified"))
    )
    (net (code "27") (name "/P10") (class "Default")
      (node (ref "J1") (pin "1") (pinfunction "1_1") (pintype "input"))
      (node (ref "LED11") (pin "1") (pinfunction "C_1") (pintype "input"))
      (node (ref "Q2") (pin "1") (pinfunction "B_1") (pintype "unspecified"))
      (node (ref "RL2") (pin "9") (pinfunction "9_9") (pintype "unspecified"))
      (node (ref "U1") (pin "1") (pinfunction "T2/P1.0_1") (pintype "unspecified"))
    )
    (net (code "28") (name "/P11") (class "Default")
      (node (ref "J1") (pin "2") (pinfunction "2_2") (pintype "input"))
      (node (ref "LED12") (pin "1") (pinfunction "C_1") (pintype "input"))
      (node (ref "RL2") (pin "8") (pinfunction "8_8") (pintype "unspecified"))
      (node (ref "U1") (pin "2") (pinfunction "T2EX/P1.1_2") (pintype "unspecified"))
    )
    (net (code "29") (name "/P12") (class "Default")
      (node (ref "J1") (pin "3") (pinfunction "3_3") (pintype "input"))
      (node (ref "LED13") (pin "1") (pinfunction "C_1") (pintype "input"))
      (node (ref "RL2") (pin "7") (pinfunction "7_7") (pintype "unspecified"))
      (node (ref "U1") (pin "3") (pinfunction "P1.2_3") (pintype "unspecified"))
    )
    (net (code "30") (name "/P13") (class "Default")
      (node (ref "J1") (pin "4") (pinfunction "4_4") (pintype "input"))
      (node (ref "LED14") (pin "1") (pinfunction "C_1") (pintype "input"))
      (node (ref "RL2") (pin "6") (pinfunction "6_6") (pintype "unspecified"))
      (node (ref "U1") (pin "4") (pinfunction "P1.3_4") (pintype "unspecified"))
    )
    (net (code "31") (name "/P14") (class "Default")
      (node (ref "J1") (pin "5") (pinfunction "5_5") (pintype "input"))
      (node (ref "LED15") (pin "1") (pinfunction "C_1") (pintype "input"))
      (node (ref "RL2") (pin "5") (pinfunction "5_5") (pintype "unspecified"))
      (node (ref "U1") (pin "5") (pinfunction "P1.4_5") (pintype "unspecified"))
    )
    (net (code "32") (name "/P15{slash}MOSI") (class "Default")
      (node (ref "J1") (pin "6") (pinfunction "6_6") (pintype "input"))
      (node (ref "LED16") (pin "1") (pinfunction "C_1") (pintype "input"))
      (node (ref "RL2") (pin "4") (pinfunction "4_4") (pintype "unspecified"))
      (node (ref "U1") (pin "6") (pinfunction "P1.5_6") (pintype "unspecified"))
    )
    (net (code "33") (name "/P16{slash}MISO") (class "Default")
      (node (ref "J1") (pin "7") (pinfunction "7_7") (pintype "input"))
      (node (ref "LED17") (pin "1") (pinfunction "C_1") (pintype "input"))
      (node (ref "RL2") (pin "3") (pinfunction "3_3") (pintype "unspecified"))
      (node (ref "U1") (pin "7") (pinfunction "P1.6_7") (pintype "unspecified"))
    )
    (net (code "34") (name "/P17{slash}SCK") (class "Default")
      (node (ref "J1") (pin "8") (pinfunction "8_8") (pintype "input"))
      (node (ref "LED18") (pin "1") (pinfunction "C_1") (pintype "input"))
      (node (ref "RL2") (pin "2") (pinfunction "2_2") (pintype "unspecified"))
      (node (ref "U1") (pin "8") (pinfunction "P1.7_8") (pintype "unspecified"))
    )
    (net (code "35") (name "/P20{slash}SDA") (class "Default")
      (node (ref "J2") (pin "20") (pinfunction "20_20") (pintype "input"))
      (node (ref "U1") (pin "21") (pinfunction "P2.0_21") (pintype "unspecified"))
    )
    (net (code "36") (name "/P21{slash}SCL") (class "Default")
      (node (ref "J2") (pin "19") (pinfunction "19_19") (pintype "input"))
      (node (ref "U1") (pin "22") (pinfunction "P2.1_22") (pintype "unspecified"))
    )
    (net (code "37") (name "/P22{slash}18B20") (class "Default")
      (node (ref "J2") (pin "18") (pinfunction "18_18") (pintype "input"))
      (node (ref "U1") (pin "23") (pinfunction "P2.2_23") (pintype "unspecified"))
    )
    (net (code "38") (name "/P23") (class "Default")
      (node (ref "J2") (pin "17") (pinfunction "17_17") (pintype "input"))
      (node (ref "R10") (pin "1") (pinfunction "1_1") (pintype "input"))
      (node (ref "U1") (pin "24") (pinfunction "P2.3_24") (pintype "unspecified"))
    )
    (net (code "39") (name "/P24") (class "Default")
      (node (ref "J2") (pin "16") (pinfunction "16_16") (pintype "input"))
      (node (ref "U1") (pin "25") (pinfunction "P2.4_25") (pintype "unspecified"))
    )
    (net (code "40") (name "/P25") (class "Default")
      (node (ref "J2") (pin "15") (pinfunction "15_15") (pintype "input"))
      (node (ref "U1") (pin "26") (pinfunction "P2.5_26") (pintype "unspecified"))
    )
    (net (code "41") (name "/P26{slash}DULA") (class "Default")
      (node (ref "J2") (pin "14") (pinfunction "14_14") (pintype "input"))
      (node (ref "U1") (pin "27") (pinfunction "P2.6_27") (pintype "unspecified"))
      (node (ref "U9") (pin "11") (pinfunction "LE_11") (pintype "unspecified"))
    )
    (net (code "42") (name "/P27{slash}WELA") (class "Default")
      (node (ref "J2") (pin "13") (pinfunction "13_13") (pintype "input"))
      (node (ref "U1") (pin "28") (pinfunction "P2.7_28") (pintype "unspecified"))
      (node (ref "U8") (pin "11") (pinfunction "LE_11") (pintype "unspecified"))
    )
    (net (code "43") (name "/P30{slash}TXD") (class "Default")
      (node (ref "D1") (pin "2") (pinfunction "A_2") (pintype "input"))
      (node (ref "J1") (pin "10") (pinfunction "10_10") (pintype "input"))
      (node (ref "LED10") (pin "1") (pinfunction "C_1") (pintype "input"))
      (node (ref "R13") (pin "1") (pinfunction "1_1") (pintype "unspecified"))
      (node (ref "S6") (pin "1") (pinfunction "1_1") (pintype "unspecified"))
      (node (ref "S7") (pin "1") (pinfunction "1_1") (pintype "unspecified"))
      (node (ref "S8") (pin "1") (pinfunction "1_1") (pintype "unspecified"))
      (node (ref "S9") (pin "1") (pinfunction "1_1") (pintype "unspecified"))
      (node (ref "U1") (pin "10") (pinfunction "RXD/P3.0_10") (pintype "unspecified"))
    )
    (net (code "44") (name "/P31{slash}RXD") (class "Default")
      (node (ref "J1") (pin "11") (pinfunction "11_11") (pintype "input"))
      (node (ref "R12") (pin "1") (pinfunction "1_1") (pintype "unspecified"))
      (node (ref "R7") (pin "1") (pinfunction "1_1") (pintype "unspecified"))
      (node (ref "S10") (pin "1") (pinfunction "1_1") (pintype "unspecified"))
      (node (ref "S11") (pin "1") (pinfunction "1_1") (pintype "unspecified"))
      (node (ref "S12") (pin "1") (pinfunction "1_1") (pintype "unspecified"))
      (node (ref "S13") (pin "1") (pinfunction "1_1") (pintype "unspecified"))
      (node (ref "U1") (pin "11") (pinfunction "TXD/P3.1_11") (pintype "unspecified"))
    )
    (net (code "45") (name "/P32{slash}INT0") (class "Default")
      (node (ref "J1") (pin "12") (pinfunction "12_12") (pintype "input"))
      (node (ref "S14") (pin "1") (pinfunction "1_1") (pintype "unspecified"))
      (node (ref "S15") (pin "1") (pinfunction "1_1") (pintype "unspecified"))
      (node (ref "S16") (pin "1") (pinfunction "1_1") (pintype "unspecified"))
      (node (ref "S17") (pin "1") (pinfunction "1_1") (pintype "unspecified"))
      (node (ref "U1") (pin "12") (pinfunction "INT0#/P3.2_12") (pintype "unspecified"))
    )
    (net (code "46") (name "/P33{slash}INT1") (class "Default")
      (node (ref "J1") (pin "13") (pinfunction "13_13") (pintype "input"))
      (node (ref "S18") (pin "1") (pinfunction "1_1") (pintype "unspecified"))
      (node (ref "S19") (pin "1") (pinfunction "1_1") (pintype "unspecified"))
      (node (ref "S20") (pin "1") (pinfunction "1_1") (pintype "unspecified"))
      (node (ref "S21") (pin "1") (pinfunction "1_1") (pintype "unspecified"))
      (node (ref "U1") (pin "13") (pinfunction "INT1#/P3.3_13") (pintype "unspecified"))
    )
    (net (code "47") (name "/P34{slash}LCDEN") (class "Default")
      (node (ref "J1") (pin "14") (pinfunction "14_14") (pintype "input"))
      (node (ref "S10") (pin "2") (pinfunction "2_2") (pintype "unspecified"))
      (node (ref "S14") (pin "2") (pinfunction "2_2") (pintype "unspecified"))
      (node (ref "S18") (pin "2") (pinfunction "2_2") (pintype "unspecified"))
      (node (ref "S6") (pin "2") (pinfunction "2_2") (pintype "unspecified"))
      (node (ref "U1") (pin "14") (pinfunction "T0/P3.4_14") (pintype "unspecified"))
    )
    (net (code "48") (name "/P35{slash}RS") (class "Default")
      (node (ref "J1") (pin "15") (pinfunction "15_15") (pintype "input"))
      (node (ref "S11") (pin "2") (pinfunction "2_2") (pintype "unspecified"))
      (node (ref "S15") (pin "2") (pinfunction "2_2") (pintype "unspecified"))
      (node (ref "S19") (pin "2") (pinfunction "2_2") (pintype "unspecified"))
      (node (ref "S7") (pin "2") (pinfunction "2_2") (pintype "unspecified"))
      (node (ref "U1") (pin "15") (pinfunction "T1/P3.5_15") (pintype "unspecified"))
    )
    (net (code "49") (name "/P36{slash}WR") (class "Default")
      (node (ref "J1") (pin "16") (pinfunction "16_16") (pintype "input"))
      (node (ref "S12") (pin "2") (pinfunction "2_2") (pintype "unspecified"))
      (node (ref "S16") (pin "2") (pinfunction "2_2") (pintype "unspecified"))
      (node (ref "S20") (pin "2") (pinfunction "2_2") (pintype "unspecified"))
      (node (ref "S8") (pin "2") (pinfunction "2_2") (pintype "unspecified"))
      (node (ref "U1") (pin "16") (pinfunction "WR#/P3.6_16") (pintype "unspecified"))
    )
    (net (code "50") (name "/P37{slash}RD") (class "Default")
      (node (ref "J1") (pin "17") (pinfunction "17_17") (pintype "input"))
      (node (ref "S13") (pin "2") (pinfunction "2_2") (pintype "unspecified"))
      (node (ref "S17") (pin "2") (pinfunction "2_2") (pintype "unspecified"))
      (node (ref "S21") (pin "2") (pinfunction "2_2") (pintype "unspecified"))
      (node (ref "S9") (pin "2") (pinfunction "2_2") (pintype "unspecified"))
      (node (ref "U1") (pin "17") (pinfunction "RD#/P3.7_17") (pintype "unspecified"))
    )
    (net (code "51") (name "/P44") (class "Default")
      (node (ref "J2") (pin "12") (pinfunction "12_12") (pintype "input"))
      (node (ref "U1") (pin "29") (pinfunction "PSEN#_29") (pintype "unspecified"))
    )
    (net (code "52") (name "/P45") (class "Default")
      (node (ref "J2") (pin "11") (pinfunction "11_11") (pintype "input"))
      (node (ref "U1") (pin "30") (pinfunction "ALE_30") (pintype "unspecified"))
    )
    (net (code "53") (name "/RST") (class "Default")
      (node (ref "EC1") (pin "2") (pinfunction "2_2") (pintype "input"))
      (node (ref "J1") (pin "9") (pinfunction "9_9") (pintype "input"))
      (node (ref "R6") (pin "1") (pinfunction "1_1") (pintype "input"))
      (node (ref "S1") (pin "2") (pinfunction "2_2") (pintype "unspecified"))
      (node (ref "U1") (pin "9") (pinfunction "RST_9") (pintype "unspecified"))
    )
    (net (code "54") (name "/RTCVDD") (class "Default")
      (node (ref "C11") (pin "1") (pinfunction "1_1") (pintype "unspecified"))
      (node (ref "MP3-IC") (pin "22") (pinfunction "RTCVDD_22") (pintype "unspecified"))
    )
    (net (code "55") (name "/RX2") (class "Default")
      (node (ref "J3") (pin "3") (pinfunction "3_3") (pintype "unspecified"))
      (node (ref "MP3-IC") (pin "7") (pinfunction "RX_7") (pintype "unspecified"))
      (node (ref "R13") (pin "2") (pinfunction "2_2") (pintype "unspecified"))
    )
    (net (code "56") (name "/SD_CLK{slash}IO7") (class "Default")
      (node (ref "J4") (pin "8") (pinfunction "8_8") (pintype "unspecified"))
      (node (ref "MP3-IC") (pin "17") (pinfunction "SD_CLK_17") (pintype "unspecified"))
    )
    (net (code "57") (name "/SD_CMD{slash}IO6") (class "Default")
      (node (ref "J4") (pin "7") (pinfunction "7_7") (pintype "unspecified"))
      (node (ref "MP3-IC") (pin "18") (pinfunction "SD_CMD_18") (pintype "unspecified"))
    )
    (net (code "58") (name "/SD_DAT{slash}IO5") (class "Default")
      (node (ref "J4") (pin "6") (pinfunction "6_6") (pintype "unspecified"))
      (node (ref "MP3-IC") (pin "19") (pinfunction "SD_DAT_19") (pintype "unspecified"))
    )
    (net (code "59") (name "/SPI-CLK") (class "Default")
      (node (ref "MP3-IC") (pin "14") (pinfunction "SPI_SCK_14") (pintype "unspecified"))
      (node (ref "SPI-Flash") (pin "6") (pinfunction "CLK_6") (pintype "unspecified"))
    )
    (net (code "60") (name "/SPI-CS") (class "Default")
      (node (ref "MP3-IC") (pin "12") (pinfunction "SPI_CS_12") (pintype "unspecified"))
      (node (ref "SPI-Flash") (pin "1") (pinfunction "CS#_1") (pintype "unspecified"))
    )
    (net (code "61") (name "/SPI-DI") (class "Default")
      (node (ref "R17") (pin "1") (pinfunction "1_1") (pintype "input"))
      (node (ref "SPI-Flash") (pin "2") (pinfunction "DO(IO1)_2") (pintype "unspecified"))
    )
    (net (code "62") (name "/SPI-DIO") (class "Default")
      (node (ref "MP3-IC") (pin "13") (pinfunction "SPI_DIO_13") (pintype "unspecified"))
    )
    (net (code "63") (name "/SPI-DO") (class "Default")
      (node (ref "R17") (pin "2") (pinfunction "2_2") (pintype "input"))
      (node (ref "SPI-Flash") (pin "5") (pinfunction "DI(IO0)_5") (pintype "unspecified"))
    )
    (net (code "64") (name "/SPK+") (class "Default")
      (node (ref "J3") (pin "8") (pinfunction "8_8") (pintype "unspecified"))
      (node (ref "SPK1") (pin "1") (pinfunction "1_1") (pintype "unspecified"))
      (node (ref "功放") (pin "8") (pinfunction "VO2_8") (pintype "unspecified"))
    )
    (net (code "65") (name "/SPK-") (class "Default")
      (node (ref "J3") (pin "7") (pinfunction "7_7") (pintype "unspecified"))
      (node (ref "R16") (pin "2") (pinfunction "2_2") (pintype "input"))
      (node (ref "SPK1") (pin "2") (pinfunction "2_2") (pintype "unspecified"))
      (node (ref "功放") (pin "5") (pinfunction "VO1_5") (pintype "unspecified"))
    )
    (net (code "66") (name "/TX2") (class "Default")
      (node (ref "J3") (pin "4") (pinfunction "4_4") (pintype "unspecified"))
      (node (ref "MP3-IC") (pin "6") (pinfunction "TX_6") (pintype "unspecified"))
      (node (ref "R12") (pin "2") (pinfunction "2_2") (pintype "unspecified"))
    )
    (net (code "67") (name "/UD+") (class "Default")
      (node (ref "U10") (pin "5") (pinfunction "D+_5") (pintype "unspecified"))
      (node (ref "USB1") (pin "3") (pinfunction "D+_3") (pintype "unspecified"))
    )
    (net (code "68") (name "/UD-") (class "Default")
      (node (ref "U10") (pin "6") (pinfunction "D-_6") (pintype "unspecified"))
      (node (ref "USB1") (pin "2") (pinfunction "D-_2") (pintype "unspecified"))
    )
    (net (code "69") (name "/USB-DM") (class "Default")
      (node (ref "MP3-IC") (pin "20") (pinfunction "USB_DM_20") (pintype "unspecified"))
      (node (ref "USB2") (pin "3") (pinfunction "D+_3") (pintype "input"))
    )
    (net (code "70") (name "/USB-DP") (class "Default")
      (node (ref "MP3-IC") (pin "21") (pinfunction "USB_DP_21") (pintype "unspecified"))
      (node (ref "USB2") (pin "2") (pinfunction "D-_2") (pintype "input"))
    )
    (net (code "71") (name "/VCOM") (class "Default")
      (node (ref "C10") (pin "1") (pinfunction "1_1") (pintype "unspecified"))
      (node (ref "MP3-IC") (pin "23") (pinfunction "VCOM_23") (pintype "unspecified"))
    )
    (net (code "72") (name "/VPP") (class "Default")
      (node (ref "J3") (pin "1") (pinfunction "1_1") (pintype "unspecified"))
      (node (ref "MP3-IC") (pin "10") (pinfunction "VPP_10") (pintype "unspecified"))
    )
    (net (code "73") (name "/WE1") (class "Default")
      (node (ref "U8") (pin "19") (pinfunction "Q0_19") (pintype "unspecified"))
      (node (ref "V5") (pin "12") (pinfunction "G1_12") (pintype "input"))
    )
    (net (code "74") (name "/WE2") (class "Default")
      (node (ref "U8") (pin "18") (pinfunction "Q1_18") (pintype "unspecified"))
      (node (ref "V5") (pin "9") (pinfunction "G2_9") (pintype "input"))
    )
    (net (code "75") (name "/WE3") (class "Default")
      (node (ref "U8") (pin "17") (pinfunction "Q2_17") (pintype "unspecified"))
      (node (ref "V5") (pin "8") (pinfunction "G3_8") (pintype "input"))
    )
    (net (code "76") (name "/WE4") (class "Default")
      (node (ref "U8") (pin "16") (pinfunction "Q3_16") (pintype "unspecified"))
      (node (ref "V5") (pin "6") (pinfunction "G4_6") (pintype "input"))
    )
    (net (code "77") (name "/WE5") (class "Default")
      (node (ref "U8") (pin "15") (pinfunction "Q4_15") (pintype "unspecified"))
      (node (ref "V6") (pin "12") (pinfunction "G1_12") (pintype "input"))
    )
    (net (code "78") (name "/WE6") (class "Default")
      (node (ref "U8") (pin "14") (pinfunction "Q5_14") (pintype "unspecified"))
      (node (ref "V6") (pin "9") (pinfunction "G2_9") (pintype "input"))
    )
    (net (code "79") (name "/WE7") (class "Default")
      (node (ref "U8") (pin "13") (pinfunction "Q6_13") (pintype "unspecified"))
      (node (ref "V6") (pin "8") (pinfunction "G3_8") (pintype "input"))
    )
    (net (code "80") (name "/WE8") (class "Default")
      (node (ref "U8") (pin "12") (pinfunction "Q7_12") (pintype "unspecified"))
      (node (ref "V6") (pin "6") (pinfunction "G4_6") (pintype "input"))
    )
    (net (code "81") (name "/XTL1") (class "Default")
      (node (ref "C8") (pin "2") (pinfunction "2_2") (pintype "unspecified"))
      (node (ref "U1") (pin "19") (pinfunction "XTAL1_19") (pintype "unspecified"))
      (node (ref "X2") (pin "2") (pinfunction "OSC2_2") (pintype "input"))
    )
    (net (code "82") (name "/XTL2") (class "Default")
      (node (ref "C9") (pin "2") (pinfunction "2_2") (pintype "unspecified"))
      (node (ref "U1") (pin "18") (pinfunction "XTAL2_18") (pintype "unspecified"))
      (node (ref "X2") (pin "1") (pinfunction "OSC1_1") (pintype "input"))
    )
    (net (code "83") (name "AGND") (class "Default")
      (node (ref "C10") (pin "2") (pinfunction "2_2") (pintype "unspecified"))
      (node (ref "C11") (pin "2") (pinfunction "2_2") (pintype "unspecified"))
      (node (ref "MP3-IC") (pin "24") (pinfunction "DACVSS_24") (pintype "unspecified"))
    )
    (net (code "84") (name "GND") (class "Default")
      (node (ref "C1") (pin "1") (pinfunction "1_1") (pintype "unspecified"))
      (node (ref "C12") (pin "1") (pinfunction "1_1") (pintype "unspecified"))
      (node (ref "C13") (pin "1") (pinfunction "1_1") (pintype "unspecified"))
      (node (ref "C16") (pin "2") (pinfunction "2_2") (pintype "unspecified"))
      (node (ref "C18") (pin "1") (pinfunction "1_1") (pintype "input"))
      (node (ref "C19") (pin "1") (pinfunction "1_1") (pintype "input"))
      (node (ref "C2") (pin "1") (pinfunction "1_1") (pintype "input"))
      (node (ref "C20") (pin "1") (pinfunction "1_1") (pintype "unspecified"))
      (node (ref "C3") (pin "1") (pinfunction "1_1") (pintype "unspecified"))
      (node (ref "C5") (pin "1") (pinfunction "1_1") (pintype "unspecified"))
      (node (ref "C6") (pin "1") (pinfunction "1_1") (pintype "unspecified"))
      (node (ref "C8") (pin "1") (pinfunction "1_1") (pintype "unspecified"))
      (node (ref "C9") (pin "1") (pinfunction "1_1") (pintype "unspecified"))
      (node (ref "EC2") (pin "2") (pinfunction "2_2") (pintype "input"))
      (node (ref "GND") (pin "1") (pinfunction "1_1") (pintype "input"))
      (node (ref "GND") (pin "2") (pinfunction "2_2") (pintype "input"))
      (node (ref "GND") (pin "3") (pinfunction "3_3") (pintype "input"))
      (node (ref "J1") (pin "18") (pinfunction "18_18") (pintype "input"))
      (node (ref "J1") (pin "19") (pinfunction "19_19") (pintype "input"))
      (node (ref "J1") (pin "20") (pinfunction "20_20") (pintype "input"))
      (node (ref "J3") (pin "5") (pinfunction "5_5") (pintype "unspecified"))
      (node (ref "K1") (pin "6") (pinfunction "6_6") (pintype "unspecified"))
      (node (ref "LED19") (pin "1") (pinfunction "C_1") (pintype "input"))
      (node (ref "LED9") (pin "1") (pinfunction "C_1") (pintype "input"))
      (node (ref "MP3-IC") (pin "5") (pinfunction "VSSIO_5") (pintype "unspecified"))
      (node (ref "R6") (pin "2") (pinfunction "2_2") (pintype "input"))
      (node (ref "SPI-Flash") (pin "4") (pinfunction "GND_4") (pintype "unspecified"))
      (node (ref "U1") (pin "20") (pinfunction "GND_20") (pintype "unspecified"))
      (node (ref "U10") (pin "1") (pinfunction "GND_1") (pintype "unspecified"))
      (node (ref "U11") (pin "2") (pinfunction "-_2") (pintype "unspecified"))
      (node (ref "U2") (pin "1") (pinfunction "GND_1") (pintype "unspecified"))
      (node (ref "U8") (pin "1") (pinfunction "OE#_1") (pintype "unspecified"))
      (node (ref "U8") (pin "10") (pinfunction "GND_10") (pintype "unspecified"))
      (node (ref "U9") (pin "1") (pinfunction "OE#_1") (pintype "unspecified"))
      (node (ref "U9") (pin "10") (pinfunction "GND_10") (pintype "unspecified"))
      (node (ref "USB1") (pin "5") (pinfunction "GND_5") (pintype "unspecified"))
      (node (ref "USB2") (pin "5") (pinfunction "GND_5") (pintype "input"))
      (node (ref "功放") (pin "1") (pinfunction "SHUTDOWN_1") (pintype "unspecified"))
      (node (ref "功放") (pin "7") (pinfunction "GND_7") (pintype "unspecified"))
      (node (ref "电磁锁") (pin "1") (pinfunction "1_1") (pintype "unspecified"))
    )
    (net (code "85") (name "Net-(C17-Pad1)") (class "Default")
      (node (ref "C17") (pin "1") (pinfunction "1_1") (pintype "unspecified"))
      (node (ref "R15") (pin "1") (pinfunction "1_1") (pintype "input"))
    )
    (net (code "86") (name "Net-(D1-K)") (class "Default")
      (node (ref "D1") (pin "1") (pinfunction "K_1") (pintype "input"))
      (node (ref "U10") (pin "2") (pinfunction "TXD_2") (pintype "unspecified"))
    )
    (net (code "87") (name "Net-(F1-Pad2)") (class "Default")
      (node (ref "F1") (pin "2") (pinfunction "2_2") (pintype "unspecified"))
      (node (ref "SW1") (pin "3") (pinfunction "3_3") (pintype "unspecified"))
    )
    (net (code "88") (name "Net-(J9-Pad1)") (class "Default")
      (node (ref "J9") (pin "1") (pinfunction "1_1") (pintype "unspecified"))
      (node (ref "RL6") (pin "1") (pinfunction "1_1") (pintype "unspecified"))
      (node (ref "RL6") (pin "2") (pinfunction "2_2") (pintype "unspecified"))
      (node (ref "RL6") (pin "3") (pinfunction "3_3") (pintype "unspecified"))
      (node (ref "RL6") (pin "4") (pinfunction "4_4") (pintype "unspecified"))
      (node (ref "RL7") (pin "1") (pinfunction "1_1") (pintype "unspecified"))
      (node (ref "RL7") (pin "2") (pinfunction "2_2") (pintype "unspecified"))
      (node (ref "RL7") (pin "3") (pinfunction "3_3") (pintype "unspecified"))
      (node (ref "RL7") (pin "4") (pinfunction "4_4") (pintype "unspecified"))
    )
    (net (code "89") (name "Net-(K1-Pad10)") (class "Default")
      (node (ref "K1") (pin "10") (pinfunction "10_10") (pintype "unspecified"))
      (node (ref "电磁锁") (pin "2") (pinfunction "2_2") (pintype "unspecified"))
    )
    (net (code "90") (name "Net-(LED9-A)") (class "Default")
      (node (ref "C1") (pin "2") (pinfunction "2_2") (pintype "unspecified"))
      (node (ref "EC2") (pin "1") (pinfunction "1_1") (pintype "input"))
      (node (ref "LED9") (pin "2") (pinfunction "A_2") (pintype "input"))
      (node (ref "SW1") (pin "1") (pinfunction "1_1") (pintype "unspecified"))
      (node (ref "U10") (pin "16") (pinfunction "VCC_16") (pintype "unspecified"))
      (node (ref "USB1") (pin "1") (pinfunction "VBUS_1") (pintype "unspecified"))
    )
    (net (code "91") (name "Net-(LED10-A)") (class "Default")
      (node (ref "LED10") (pin "2") (pinfunction "A_2") (pintype "input"))
      (node (ref "R1") (pin "1") (pinfunction "1_1") (pintype "input"))
    )
    (net (code "92") (name "Net-(LED11-A)") (class "Default")
      (node (ref "LED11") (pin "2") (pinfunction "A_2") (pintype "input"))
      (node (ref "RL6") (pin "8") (pinfunction "8_8") (pintype "unspecified"))
    )
    (net (code "93") (name "Net-(LED12-A)") (class "Default")
      (node (ref "LED12") (pin "2") (pinfunction "A_2") (pintype "input"))
      (node (ref "RL6") (pin "7") (pinfunction "7_7") (pintype "unspecified"))
    )
    (net (code "94") (name "Net-(LED13-A)") (class "Default")
      (node (ref "LED13") (pin "2") (pinfunction "A_2") (pintype "input"))
      (node (ref "RL6") (pin "6") (pinfunction "6_6") (pintype "unspecified"))
    )
    (net (code "95") (name "Net-(LED14-A)") (class "Default")
      (node (ref "LED14") (pin "2") (pinfunction "A_2") (pintype "input"))
      (node (ref "RL6") (pin "5") (pinfunction "5_5") (pintype "unspecified"))
    )
    (net (code "96") (name "Net-(LED15-A)") (class "Default")
      (node (ref "LED15") (pin "2") (pinfunction "A_2") (pintype "input"))
      (node (ref "RL7") (pin "8") (pinfunction "8_8") (pintype "unspecified"))
    )
    (net (code "97") (name "Net-(LED16-A)") (class "Default")
      (node (ref "LED16") (pin "2") (pinfunction "A_2") (pintype "input"))
      (node (ref "RL7") (pin "7") (pinfunction "7_7") (pintype "unspecified"))
    )
    (net (code "98") (name "Net-(LED17-A)") (class "Default")
      (node (ref "LED17") (pin "2") (pinfunction "A_2") (pintype "input"))
      (node (ref "RL7") (pin "6") (pinfunction "6_6") (pintype "unspecified"))
    )
    (net (code "99") (name "Net-(LED18-A)") (class "Default")
      (node (ref "LED18") (pin "2") (pinfunction "A_2") (pintype "input"))
      (node (ref "RL7") (pin "5") (pinfunction "5_5") (pintype "unspecified"))
    )
    (net (code "100") (name "Net-(LED19-A)") (class "Default")
      (node (ref "LED19") (pin "2") (pinfunction "A_2") (pintype "input"))
      (node (ref "R14") (pin "2") (pinfunction "2_2") (pintype "unspecified"))
    )
    (net (code "101") (name "Net-(Q1-B)") (class "Default")
      (node (ref "Q1") (pin "1") (pinfunction "B_1") (pintype "unspecified"))
      (node (ref "R10") (pin "2") (pinfunction "2_2") (pintype "input"))
    )
    (net (code "102") (name "Net-(Q1-C)") (class "Default")
      (node (ref "Q1") (pin "3") (pinfunction "C_3") (pintype "unspecified"))
      (node (ref "U11") (pin "1") (pinfunction "+_1") (pintype "unspecified"))
    )
    (net (code "103") (name "Net-(Q2-C)") (class "Default")
      (node (ref "K1") (pin "1") (pinfunction "1_1") (pintype "unspecified"))
      (node (ref "Q2") (pin "3") (pinfunction "C_3") (pintype "unspecified"))
    )
    (net (code "104") (name "Net-(U9-Q0)") (class "Default")
      (node (ref "RL3") (pin "1") (pinfunction "1_1") (pintype "unspecified"))
      (node (ref "U9") (pin "19") (pinfunction "Q0_19") (pintype "unspecified"))
    )
    (net (code "105") (name "Net-(U9-Q1)") (class "Default")
      (node (ref "RL3") (pin "2") (pinfunction "2_2") (pintype "unspecified"))
      (node (ref "U9") (pin "18") (pinfunction "Q1_18") (pintype "unspecified"))
    )
    (net (code "106") (name "Net-(U9-Q2)") (class "Default")
      (node (ref "RL3") (pin "3") (pinfunction "3_3") (pintype "unspecified"))
      (node (ref "U9") (pin "17") (pinfunction "Q2_17") (pintype "unspecified"))
    )
    (net (code "107") (name "Net-(U9-Q3)") (class "Default")
      (node (ref "RL3") (pin "4") (pinfunction "4_4") (pintype "unspecified"))
      (node (ref "U9") (pin "16") (pinfunction "Q3_16") (pintype "unspecified"))
    )
    (net (code "108") (name "Net-(U9-Q4)") (class "Default")
      (node (ref "RL4") (pin "1") (pinfunction "1_1") (pintype "unspecified"))
      (node (ref "U9") (pin "15") (pinfunction "Q4_15") (pintype "unspecified"))
    )
    (net (code "109") (name "Net-(U9-Q5)") (class "Default")
      (node (ref "RL4") (pin "2") (pinfunction "2_2") (pintype "unspecified"))
      (node (ref "U9") (pin "14") (pinfunction "Q5_14") (pintype "unspecified"))
    )
    (net (code "110") (name "Net-(U9-Q6)") (class "Default")
      (node (ref "RL4") (pin "3") (pinfunction "3_3") (pintype "unspecified"))
      (node (ref "U9") (pin "13") (pinfunction "Q6_13") (pintype "unspecified"))
    )
    (net (code "111") (name "Net-(U9-Q7)") (class "Default")
      (node (ref "RL4") (pin "4") (pinfunction "4_4") (pintype "unspecified"))
      (node (ref "U9") (pin "12") (pinfunction "Q7_12") (pintype "unspecified"))
    )
    (net (code "112") (name "Net-(U10-RTS#)") (class "Default")
      (node (ref "J0") (pin "1") (pinfunction "1_1") (pintype "unspecified"))
      (node (ref "U10") (pin "14") (pinfunction "RTS#_14") (pintype "unspecified"))
    )
    (net (code "113") (name "Net-(U10-RXD)") (class "Default")
      (node (ref "R7") (pin "2") (pinfunction "2_2") (pintype "unspecified"))
      (node (ref "U10") (pin "3") (pinfunction "RXD_3") (pintype "unspecified"))
    )
    (net (code "114") (name "Net-(U10-V3)") (class "Default")
      (node (ref "C2") (pin "2") (pinfunction "2_2") (pintype "input"))
      (node (ref "U10") (pin "4") (pinfunction "V3_4") (pintype "unspecified"))
    )
    (net (code "115") (name "Net-(功放-+IN)") (class "Default")
      (node (ref "C16") (pin "1") (pinfunction "1_1") (pintype "unspecified"))
      (node (ref "功放") (pin "2") (pinfunction "BYPASS_2") (pintype "unspecified"))
      (node (ref "功放") (pin "3") (pinfunction "+IN_3") (pintype "unspecified"))
    )
    (net (code "116") (name "Net-(功放--IN)") (class "Default")
      (node (ref "R15") (pin "2") (pinfunction "2_2") (pintype "input"))
      (node (ref "R16") (pin "1") (pinfunction "1_1") (pintype "input"))
      (node (ref "功放") (pin "4") (pinfunction "-IN_4") (pintype "unspecified"))
    )
    (net (code "117") (name "VCC") (class "Default")
      (node (ref "5V0") (pin "1") (pinfunction "1_1") (pintype "input"))
      (node (ref "5V0") (pin "2") (pinfunction "2_2") (pintype "input"))
      (node (ref "5V0") (pin "3") (pinfunction "3_3") (pintype "input"))
      (node (ref "C5") (pin "2") (pinfunction "2_2") (pintype "unspecified"))
      (node (ref "C6") (pin "2") (pinfunction "2_2") (pintype "unspecified"))
      (node (ref "D2") (pin "2") (pinfunction "A_2") (pintype "input"))
      (node (ref "EC1") (pin "1") (pinfunction "1_1") (pintype "input"))
      (node (ref "F1") (pin "1") (pinfunction "1_1") (pintype "unspecified"))
      (node (ref "J2") (pin "1") (pinfunction "1_1") (pintype "input"))
      (node (ref "J2") (pin "10") (pinfunction "10_10") (pintype "input"))
      (node (ref "J3") (pin "6") (pinfunction "6_6") (pintype "unspecified"))
      (node (ref "J9") (pin "2") (pinfunction "2_2") (pintype "unspecified"))
      (node (ref "K1") (pin "7") (pinfunction "7_7") (pintype "unspecified"))
      (node (ref "Q1") (pin "2") (pinfunction "E_2") (pintype "unspecified"))
      (node (ref "R1") (pin "2") (pinfunction "2_2") (pintype "input"))
      (node (ref "RL1") (pin "1") (pinfunction "1_1") (pintype "unspecified"))
      (node (ref "RL2") (pin "1") (pinfunction "1_1") (pintype "unspecified"))
      (node (ref "S1") (pin "1") (pinfunction "1_1") (pintype "unspecified"))
      (node (ref "U1") (pin "31") (pinfunction "EA#_31") (pintype "unspecified"))
      (node (ref "U1") (pin "40") (pinfunction "VCC_40") (pintype "unspecified"))
      (node (ref "U2") (pin "3") (pinfunction "VIN_3") (pintype "unspecified"))
      (node (ref "U8") (pin "20") (pinfunction "VCC_20") (pintype "unspecified"))
      (node (ref "U9") (pin "20") (pinfunction "VCC_20") (pintype "unspecified"))
      (node (ref "USB2") (pin "1") (pinfunction "VCC_1") (pintype "input"))
    )
    (net (code "118") (name "VMCU") (class "Default")
      (node (ref "C12") (pin "2") (pinfunction "2_2") (pintype "unspecified"))
      (node (ref "C18") (pin "2") (pinfunction "2_2") (pintype "input"))
      (node (ref "C19") (pin "2") (pinfunction "2_2") (pintype "input"))
      (node (ref "D2") (pin "1") (pinfunction "K_1") (pintype "input"))
      (node (ref "MP3-IC") (pin "4") (pinfunction "VMCU_4") (pintype "unspecified"))
      (node (ref "功放") (pin "6") (pinfunction "VDD_6") (pintype "unspecified"))
    )
    (net (code "119") (name "unconnected-(J0-Pad2)") (class "Default")
      (node (ref "J0") (pin "2") (pinfunction "2_2") (pintype "unspecified+no_connect"))
    )
    (net (code "120") (name "unconnected-(K1-Pad12)") (class "Default")
      (node (ref "K1") (pin "12") (pinfunction "12_12") (pintype "unspecified+no_connect"))
    )
    (net (code "121") (name "unconnected-(SW1-Pad2)") (class "Default")
      (node (ref "SW1") (pin "2") (pinfunction "2_2") (pintype "unspecified+no_connect"))
    )
    (net (code "122") (name "unconnected-(SW1-Pad4)") (class "Default")
      (node (ref "SW1") (pin "4") (pinfunction "4_4") (pintype "unspecified+no_connect"))
    )
    (net (code "123") (name "unconnected-(SW1-Pad5)") (class "Default")
      (node (ref "SW1") (pin "5") (pinfunction "5_5") (pintype "unspecified+no_connect"))
    )
    (net (code "124") (name "unconnected-(SW1-Pad6)") (class "Default")
      (node (ref "SW1") (pin "6") (pinfunction "6_6") (pintype "unspecified+no_connect"))
    )
    (net (code "125") (name "unconnected-(U2-TAB-Pad4)") (class "Default")
      (node (ref "U2") (pin "4") (pinfunction "TAB_4") (pintype "unspecified+no_connect"))
    )
    (net (code "126") (name "unconnected-(U10-CTS#-Pad9)") (class "Default")
      (node (ref "U10") (pin "9") (pinfunction "CTS#_9") (pintype "unspecified+no_connect"))
    )
    (net (code "127") (name "unconnected-(U10-DCD#-Pad12)") (class "Default")
      (node (ref "U10") (pin "12") (pinfunction "DCD#_12") (pintype "unspecified+no_connect"))
    )
    (net (code "128") (name "unconnected-(U10-DSR#-Pad10)") (class "Default")
      (node (ref "U10") (pin "10") (pinfunction "DSR#_10") (pintype "unspecified+no_connect"))
    )
    (net (code "129") (name "unconnected-(U10-DTR#-Pad13)") (class "Default")
      (node (ref "U10") (pin "13") (pinfunction "DTR#_13") (pintype "unspecified+no_connect"))
    )
    (net (code "130") (name "unconnected-(U10-NC.-Pad7)") (class "Default")
      (node (ref "U10") (pin "7") (pinfunction "NC._7") (pintype "unspecified+no_connect"))
    )
    (net (code "131") (name "unconnected-(U10-OUT#-Pad8)") (class "Default")
      (node (ref "U10") (pin "8") (pinfunction "OUT#_8") (pintype "unspecified+no_connect"))
    )
    (net (code "132") (name "unconnected-(U10-R232-Pad15)") (class "Default")
      (node (ref "U10") (pin "15") (pinfunction "R232_15") (pintype "unspecified+no_connect"))
    )
    (net (code "133") (name "unconnected-(U10-RI#-Pad11)") (class "Default")
      (node (ref "U10") (pin "11") (pinfunction "RI#_11") (pintype "unspecified+no_connect"))
    )
    (net (code "134") (name "unconnected-(USB1-EP-Pad6)") (class "Default")
      (node (ref "USB1") (pin "6") (pinfunction "EP_6") (pintype "unspecified+no_connect"))
    )
    (net (code "135") (name "unconnected-(USB1-EP-Pad7)") (class "Default")
      (node (ref "USB1") (pin "7") (pinfunction "EP_7") (pintype "unspecified+no_connect"))
    )
    (net (code "136") (name "unconnected-(USB1-EP-Pad8)") (class "Default")
      (node (ref "USB1") (pin "8") (pinfunction "EP_8") (pintype "unspecified+no_connect"))
    )
    (net (code "137") (name "unconnected-(USB1-EP-Pad9)") (class "Default")
      (node (ref "USB1") (pin "9") (pinfunction "EP_9") (pintype "unspecified+no_connect"))
    )
    (net (code "138") (name "unconnected-(USB1-ID-Pad4)") (class "Default")
      (node (ref "USB1") (pin "4") (pinfunction "ID_4") (pintype "unspecified+no_connect"))
    )
    (net (code "139") (name "unconnected-(USB2-EH-Pad6)") (class "Default")
      (node (ref "USB2") (pin "6") (pinfunction "EH_6") (pintype "unspecified+no_connect"))
    )
    (net (code "140") (name "unconnected-(USB2-EH-Pad7)") (class "Default")
      (node (ref "USB2") (pin "7") (pinfunction "EH_7") (pintype "unspecified+no_connect"))
    )
    (net (code "141") (name "unconnected-(USB2-EH-Pad8)") (class "Default")
      (node (ref "USB2") (pin "8") (pinfunction "EH_8") (pintype "unspecified+no_connect"))
    )
    (net (code "142") (name "unconnected-(USB2-EH-Pad9)") (class "Default")
      (node (ref "USB2") (pin "9") (pinfunction "EH_9") (pintype "unspecified+no_connect"))
    )
    (net (code "143") (name "unconnected-(USB2-ID-Pad4)") (class "Default")
      (node (ref "USB2") (pin "4") (pinfunction "ID_4") (pintype "input+no_connect"))
    )
  )
)
